# Raumluftsensor.net
KiCad netlist of a schematic drawn in Altium Designer
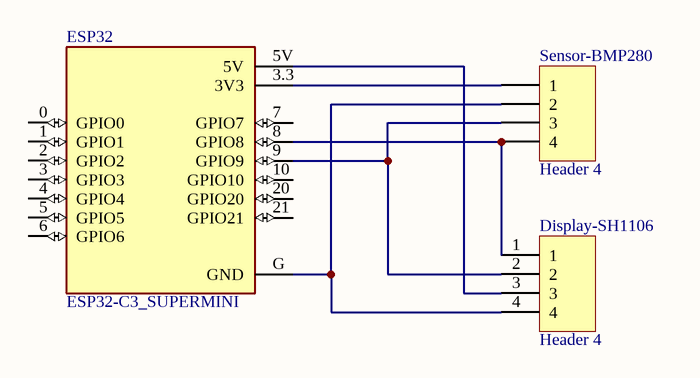
[diagram p0: Raumluftsensor.SchDoc]

(export (version "E")
  (design (tool "Eeschema 10.0.6"))
  (components
    (comp (ref "Display-SH1106")
      (value "Header 4")
      (footprint "HDR1X4")
      (description "Header, 4-Pin")
      (fields (field (name "PUBLISHER") "Altium Limited"))
      (libsource (lib "Miscellaneous Connectors") (part "Header 4"))
    )
    (comp (ref "ESP32")
      (value "ESP32-C3_SUPERMINI")
      (footprint "MODULE_ESP32-C3_SUPERMINI")
      (description "Super tiny ESP32-C3 board")
      (fields (field (name "MF") "Espressif Systems") (field (name "MP") "ESP32-C3 SuperMini_TH"))
      (libsource (lib "ESP32-C3_SUPERMINI_TH") (part "ESP32-C3_SUPERMINI_TH"))
    )
    (comp (ref "Sensor-BMP280")
      (value "Header 4")
      (footprint "HDR1X4")
      (description "Header, 4-Pin")
      (fields (field (name "PUBLISHER") "Altium Limited"))
      (libsource (lib "") (part "Header 4_1"))
    )
  )
  (nets
    (net (code "1") (name "Net-(Display-SH1106-Pad3)") (class "Default")
      (node (ref "Display-SH1106") (pin "3") (pinfunction "3_3") (pintype "passive"))
      (node (ref "ESP32") (pin "5V") (pinfunction "5V_5V") (pintype "power_in"))
    )
    (net (code "2") (name "Net-(ESP32-3V3)") (class "Default")
      (node (ref "ESP32") (pin "3.3") (pinfunction "3V3_3.3") (pintype "power_in"))
      (node (ref "Sensor-BMP280") (pin "1") (pinfunction "1_1") (pintype "passive"))
    )
    (net (code "3") (name "Net-(ESP32-GND)") (class "Default")
      (node (ref "Display-SH1106") (pin "4") (pinfunction "4_4") (pintype "passive"))
      (node (ref "ESP32") (pin "G") (pinfunction "GND_G") (pintype "power_in"))
      (node (ref "Sensor-BMP280") (pin "2") (pinfunction "2_2") (pintype "passive"))
    )
    (net (code "4") (name "Net-(ESP32-GPIO8)") (class "Default")
      (node (ref "Display-SH1106") (pin "1") (pinfunction "1_1") (pintype "passive"))
      (node (ref "ESP32") (pin "8") (pinfunction "GPIO8_8") (pintype "bidirectional"))
      (node (ref "Sensor-BMP280") (pin "4") (pinfunction "4_4") (pintype "passive"))
    )
    (net (code "5") (name "Net-(ESP32-GPIO9)") (class "Default")
      (node (ref "Display-SH1106") (pin "2") (pinfunction "2_2") (pintype "passive"))
      (node (ref "ESP32") (pin "9") (pinfunction "GPIO9_9") (pintype "bidirectional"))
      (node (ref "Sensor-BMP280") (pin "3") (pinfunction "3_3") (pintype "passive"))
    )
    (net (code "6") (name "unconnected-(ESP32-GPIO0-Pad0)") (class "Default")
      (node (ref "ESP32") (pin "0") (pinfunction "GPIO0_0") (pintype "bidirectional"))
    )
    (net (code "7") (name "unconnected-(ESP32-GPIO1-Pad1)") (class "Default")
      (node (ref "ESP32") (pin "1") (pinfunction "GPIO1_1") (pintype "bidirectional"))
    )
    (net (code "8") (name "unconnected-(ESP32-GPIO2-Pad2)") (class "Default")
      (node (ref "ESP32") (pin "2") (pinfunction "GPIO2_2") (pintype "bidirectional"))
    )
    (net (code "9") (name "unconnected-(ESP32-GPIO3-Pad3)") (class "Default")
      (node (ref "ESP32") (pin "3") (pinfunction "GPIO3_3") (pintype "bidirectional"))
    )
    (net (code "10") (name "unconnected-(ESP32-GPIO4-Pad4)") (class "Default")
      (node (ref "ESP32") (pin "4") (pinfunction "GPIO4_4") (pintype "bidirectional"))
    )
    (net (code "11") (name "unconnected-(ESP32-GPIO5-Pad5)") (class "Default")
      (node (ref "ESP32") (pin "5") (pinfunction "GPIO5_5") (pintype "bidirectional"))
    )
    (net (code "12") (name "unconnected-(ESP32-GPIO6-Pad6)") (class "Default")
      (node (ref "ESP32") (pin "6") (pinfunction "GPIO6_6") (pintype "bidirectional"))
    )
    (net (code "13") (name "unconnected-(ESP32-GPIO7-Pad7)") (class "Default")
      (node (ref "ESP32") (pin "7") (pinfunction "GPIO7_7") (pintype "bidirectional"))
    )
    (net (code "14") (name "unconnected-(ESP32-GPIO10-Pad10)") (class "Default")
      (node (ref "ESP32") (pin "10") (pinfunction "GPIO10_10") (pintype "bidirectional"))
    )
    (net (code "15") (name "unconnected-(ESP32-GPIO20-Pad20)") (class "Default")
      (node (ref "ESP32") (pin "20") (pinfunction "GPIO20_20") (pintype "bidirectional"))
    )
    (net (code "16") (name "unconnected-(ESP32-GPIO21-Pad21)") (class "Default")
      (node (ref "ESP32") (pin "21") (pinfunction "GPIO21_21") (pintype "bidirectional"))
    )
  )
)
